# ArduinoRadioV2.net
KiCad netlist of a schematic drawn in EAGLE
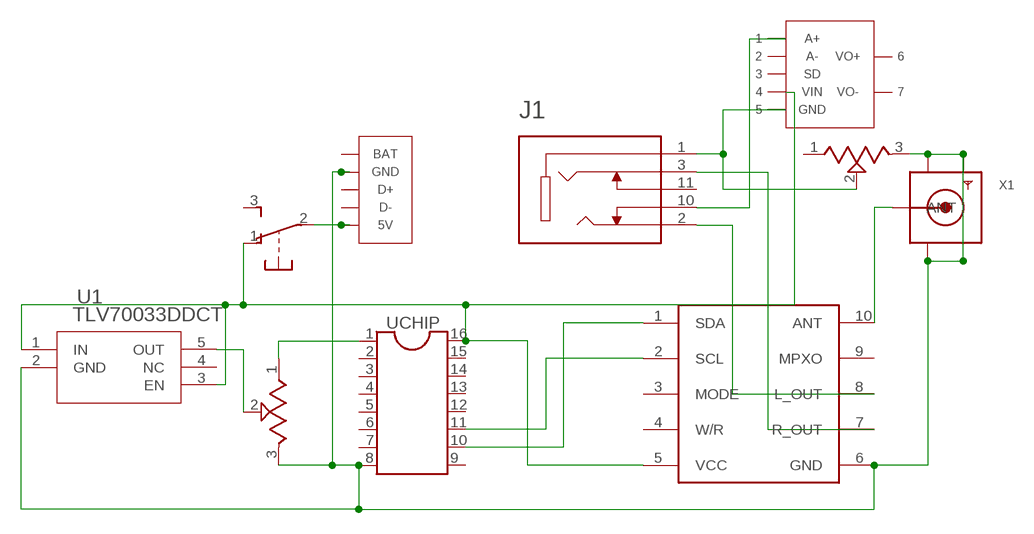
[diagram p0: schematic, sheet 1]

(export (version "E")
  (design (tool "Eeschema 10.0.6"))
  (components
    (comp (ref "IC1")
      (value "UCHIP")
      (footprint "eagle-import:UCHIP")
      (libsource (lib "eagle-import") (part "UCHIP"))
    )
    (comp (ref "J1")
      (value "SJ1-3525N")
      (footprint "eagle-import:CUI_SJ1-3525N")
      (fields (field (name "MF") "CUI Devices"))
      (libsource (lib "eagle-import") (part "SJ1-3525N"))
    )
    (comp (ref "S1")
      (value "EG1213")
      (footprint "eagle-import:EG1213")
      (libsource (lib "eagle-import") (part "EG1213"))
    )
    (comp (ref "TEA5767")
      (value "TEA5767BREAKOUT")
      (footprint "eagle-import:TEA5767MM2")
      (libsource (lib "eagle-import") (part "TEA5767BREAKOUT"))
    )
    (comp (ref "TUNE")
      (value "3352T-1-103LF")
      (footprint "eagle-import:TRIM_3352T-1-103LF")
      (fields (field (name "DIGI-KEY_PART_NUMBER") "3352T-103LF-ND") (field (name "MF") "Bourns"))
      (libsource (lib "eagle-import") (part "3352T-1-103LF"))
    )
    (comp (ref "U$1")
      (value "AMP")
      (footprint "eagle-import:AMP")
      (libsource (lib "eagle-import") (part "AMP"))
    )
    (comp (ref "U$2")
      (value "MICROLIPO")
      (footprint "eagle-import:MICROLIPO")
      (libsource (lib "eagle-import") (part "MICROLIPO"))
    )
    (comp (ref "U1")
      (value "TLV70033DDCT")
      (footprint "eagle-import:DDC5")
      (fields (field (name "MANUFACTURER") "Texas Instruments"))
      (libsource (lib "eagle-import") (part "TLV70033DDCT"))
    )
    (comp (ref "VOL")
      (value "3352T-1-103LF")
      (footprint "eagle-import:TRIM_3352T-1-103LF")
      (fields (field (name "DIGI-KEY_PART_NUMBER") "3352T-103LF-ND") (field (name "MF") "Bourns"))
      (libsource (lib "eagle-import") (part "3352T-1-103LF"))
    )
    (comp (ref "X1")
      (value "SMACONNECTOR")
      (footprint "eagle-import:SMA90_DIP")
      (libsource (lib "eagle-import") (part "SMACONNECTOR"))
    )
  )
  (nets
    (net (code "1") (name "Net-(IC1-D1{slash}A1)") (class "Default")
      (node (ref "IC1") (pin "1") (pinfunction "D1/A1_1") (pintype "passive"))
      (node (ref "TUNE") (pin "1") (pinfunction "CCW_1") (pintype "passive"))
    )
    (net (code "2") (name "Net-(IC1-D10)") (class "Default")
      (node (ref "IC1") (pin "10") (pinfunction "D10_10") (pintype "passive"))
      (node (ref "TEA5767") (pin "1") (pinfunction "SDA_1") (pintype "bidirectional"))
    )
    (net (code "3") (name "Net-(IC1-D11)") (class "Default")
      (node (ref "IC1") (pin "11") (pinfunction "D11_11") (pintype "passive"))
      (node (ref "TEA5767") (pin "2") (pinfunction "SCL_2") (pintype "bidirectional"))
    )
    (net (code "4") (name "Net-(IC1-GND)") (class "Default")
      (node (ref "IC1") (pin "8") (pinfunction "GND_8") (pintype "passive"))
      (node (ref "TEA5767") (pin "6") (pinfunction "GND_6") (pintype "bidirectional"))
      (node (ref "TUNE") (pin "3") (pinfunction "CW_3") (pintype "passive"))
      (node (ref "U$2") (pin "P$1") (pinfunction "GND_P$1") (pintype "bidirectional"))
      (node (ref "U$2") (pin "P$2") (pinfunction "GND_P$2") (pintype "bidirectional"))
      (node (ref "U$2") (pin "P$3") (pinfunction "GND_P$3") (pintype "bidirectional"))
      (node (ref "U$2") (pin "P$4") (pinfunction "GND_P$4") (pintype "bidirectional"))
      (node (ref "U$2") (pin "P$8") (pinfunction "GND_P$8") (pintype "bidirectional"))
      (node (ref "U1") (pin "2") (pinfunction "GND_2") (pintype "power_in"))
      (node (ref "VOL") (pin "3") (pinfunction "CW_3") (pintype "passive"))
      (node (ref "X1") (pin "GND1") (pinfunction "GND1_GND1") (pintype "power_in"))
      (node (ref "X1") (pin "GND2") (pinfunction "GND2_GND2") (pintype "power_in"))
      (node (ref "X1") (pin "GND3") (pinfunction "GND3_GND3") (pintype "power_in"))
      (node (ref "X1") (pin "GND4") (pinfunction "GND4_GND4") (pintype "power_in"))
    )
    (net (code "5") (name "Net-(IC1-V_EXT)") (class "Default")
      (node (ref "IC1") (pin "16") (pinfunction "V_EXT_16") (pintype "passive"))
      (node (ref "S1") (pin "1") (pinfunction "O_1") (pintype "passive"))
      (node (ref "TEA5767") (pin "5") (pinfunction "VCC_5") (pintype "bidirectional"))
      (node (ref "U$1") (pin "VIN") (pinfunction "4_VIN") (pintype "bidirectional"))
      (node (ref "U1") (pin "1") (pinfunction "IN_1") (pintype "input"))
      (node (ref "U1") (pin "3") (pinfunction "EN_3") (pintype "passive"))
    )
    (net (code "6") (name "Net-(S1A-P)") (class "Default")
      (node (ref "S1") (pin "2") (pinfunction "P_2") (pintype "passive"))
      (node (ref "U$2") (pin "P$5") (pinfunction "5V_P$5") (pintype "bidirectional"))
    )
    (net (code "7") (name "Net-(TEA5767-ANT)") (class "Default")
      (node (ref "TEA5767") (pin "10") (pinfunction "ANT_10") (pintype "bidirectional"))
      (node (ref "X1") (pin "ANTENNA") (pinfunction "ANT_ANTENNA") (pintype "bidirectional"))
    )
    (net (code "8") (name "Net-(TEA5767-L_OUT)") (class "Default")
      (node (ref "J1") (pin "2") (pinfunction "2_2") (pintype "passive"))
      (node (ref "TEA5767") (pin "8") (pinfunction "L_OUT_8") (pintype "bidirectional"))
    )
    (net (code "9") (name "Net-(TEA5767-R_OUT)") (class "Default")
      (node (ref "J1") (pin "3") (pinfunction "3_3") (pintype "passive"))
      (node (ref "TEA5767") (pin "7") (pinfunction "R_OUT_7") (pintype "bidirectional"))
    )
    (net (code "10") (name "Net-(TUNE-WIPER)") (class "Default")
      (node (ref "TUNE") (pin "2") (pinfunction "WIPER_2") (pintype "passive"))
      (node (ref "U1") (pin "5") (pinfunction "OUT_5") (pintype "output"))
    )
    (net (code "11") (name "Net-(U$1-1)") (class "Default")
      (node (ref "J1") (pin "10") (pinfunction "10_10") (pintype "passive"))
      (node (ref "U$1") (pin "A+") (pinfunction "1_A+") (pintype "bidirectional"))
    )
    (net (code "12") (name "Net-(U$1-5)") (class "Default")
      (node (ref "J1") (pin "1") (pinfunction "1_1") (pintype "passive"))
      (node (ref "U$1") (pin "GND") (pinfunction "5_GND") (pintype "bidirectional"))
      (node (ref "VOL") (pin "2") (pinfunction "WIPER_2") (pintype "passive"))
    )
    (net (code "13") (name "unconnected-(IC1-D2{slash}A2-Pad2)") (class "Default")
      (node (ref "IC1") (pin "2") (pinfunction "D2/A2_2") (pintype "passive"))
    )
    (net (code "14") (name "unconnected-(IC1-D3{slash}A3-Pad3)") (class "Default")
      (node (ref "IC1") (pin "3") (pinfunction "D3/A3_3") (pintype "passive"))
    )
    (net (code "15") (name "unconnected-(IC1-D4{slash}A4-Pad4)") (class "Default")
      (node (ref "IC1") (pin "4") (pinfunction "D4/A4_4") (pintype "passive"))
    )
    (net (code "16") (name "unconnected-(IC1-D5{slash}A5-Pad5)") (class "Default")
      (node (ref "IC1") (pin "5") (pinfunction "D5/A5_5") (pintype "passive"))
    )
    (net (code "17") (name "unconnected-(IC1-D6-Pad6)") (class "Default")
      (node (ref "IC1") (pin "6") (pinfunction "D6_6") (pintype "passive"))
    )
    (net (code "18") (name "unconnected-(IC1-D7-Pad7)") (class "Default")
      (node (ref "IC1") (pin "7") (pinfunction "D7_7") (pintype "passive"))
    )
    (net (code "19") (name "unconnected-(IC1-D9-Pad9)") (class "Default")
      (node (ref "IC1") (pin "9") (pinfunction "D9_9") (pintype "passive"))
    )
    (net (code "20") (name "unconnected-(IC1-D12-Pad12)") (class "Default")
      (node (ref "IC1") (pin "12") (pinfunction "D12_12") (pintype "passive"))
    )
    (net (code "21") (name "unconnected-(IC1-D13-Pad13)") (class "Default")
      (node (ref "IC1") (pin "13") (pinfunction "D13_13") (pintype "passive"))
    )
    (net (code "22") (name "unconnected-(IC1-D14{slash}A14-Pad14)") (class "Default")
      (node (ref "IC1") (pin "14") (pinfunction "D14/A14_14") (pintype "passive"))
    )
    (net (code "23") (name "unconnected-(IC1-D15{slash}A15-Pad15)") (class "Default")
      (node (ref "IC1") (pin "15") (pinfunction "D15/A15_15") (pintype "passive"))
    )
    (net (code "24") (name "unconnected-(J1-Pad11)") (class "Default")
      (node (ref "J1") (pin "11") (pinfunction "11_11") (pintype "passive"))
    )
    (net (code "25") (name "unconnected-(S1A-S-Pad3)") (class "Default")
      (node (ref "S1") (pin "3") (pinfunction "S_3") (pintype "passive"))
    )
    (net (code "26") (name "unconnected-(TEA5767-MODE-Pad3)") (class "Default")
      (node (ref "TEA5767") (pin "3") (pinfunction "MODE_3") (pintype "bidirectional"))
    )
    (net (code "27") (name "unconnected-(TEA5767-MPXO-Pad9)") (class "Default")
      (node (ref "TEA5767") (pin "9") (pinfunction "MPXO_9") (pintype "bidirectional"))
    )
    (net (code "28") (name "unconnected-(TEA5767-W{slash}R-Pad4)") (class "Default")
      (node (ref "TEA5767") (pin "4") (pinfunction "W/R_4") (pintype "bidirectional"))
    )
    (net (code "29") (name "unconnected-(U$1-2-PadA-)") (class "Default")
      (node (ref "U$1") (pin "A-") (pinfunction "2_A-") (pintype "bidirectional"))
    )
    (net (code "30") (name "unconnected-(U$1-3-PadSD)") (class "Default")
      (node (ref "U$1") (pin "SD") (pinfunction "3_SD") (pintype "bidirectional"))
    )
    (net (code "31") (name "unconnected-(U$1-6-PadVO+)") (class "Default")
      (node (ref "U$1") (pin "VO+") (pinfunction "6_VO+") (pintype "bidirectional"))
    )
    (net (code "32") (name "unconnected-(U$1-7-PadVO-)") (class "Default")
      (node (ref "U$1") (pin "VO-") (pinfunction "7_VO-") (pintype "bidirectional"))
    )
    (net (code "33") (name "unconnected-(U$2-BAT-PadP$9)") (class "Default")
      (node (ref "U$2") (pin "P$9") (pinfunction "BAT_P$9") (pintype "bidirectional"))
    )
    (net (code "34") (name "unconnected-(U$2-D+-PadP$7)") (class "Default")
      (node (ref "U$2") (pin "P$7") (pinfunction "D+_P$7") (pintype "bidirectional"))
    )
    (net (code "35") (name "unconnected-(U$2-D--PadP$6)") (class "Default")
      (node (ref "U$2") (pin "P$6") (pinfunction "D-_P$6") (pintype "bidirectional"))
    )
    (net (code "36") (name "unconnected-(U1-NC-Pad4)") (class "Default")
      (node (ref "U1") (pin "4") (pinfunction "NC_4") (pintype "passive"))
    )
    (net (code "37") (name "unconnected-(VOL-CCW-Pad1)") (class "Default")
      (node (ref "VOL") (pin "1") (pinfunction "CCW_1") (pintype "passive"))
    )
  )
)
